# combined.net
KiCad netlist of a schematic drawn in EAGLE
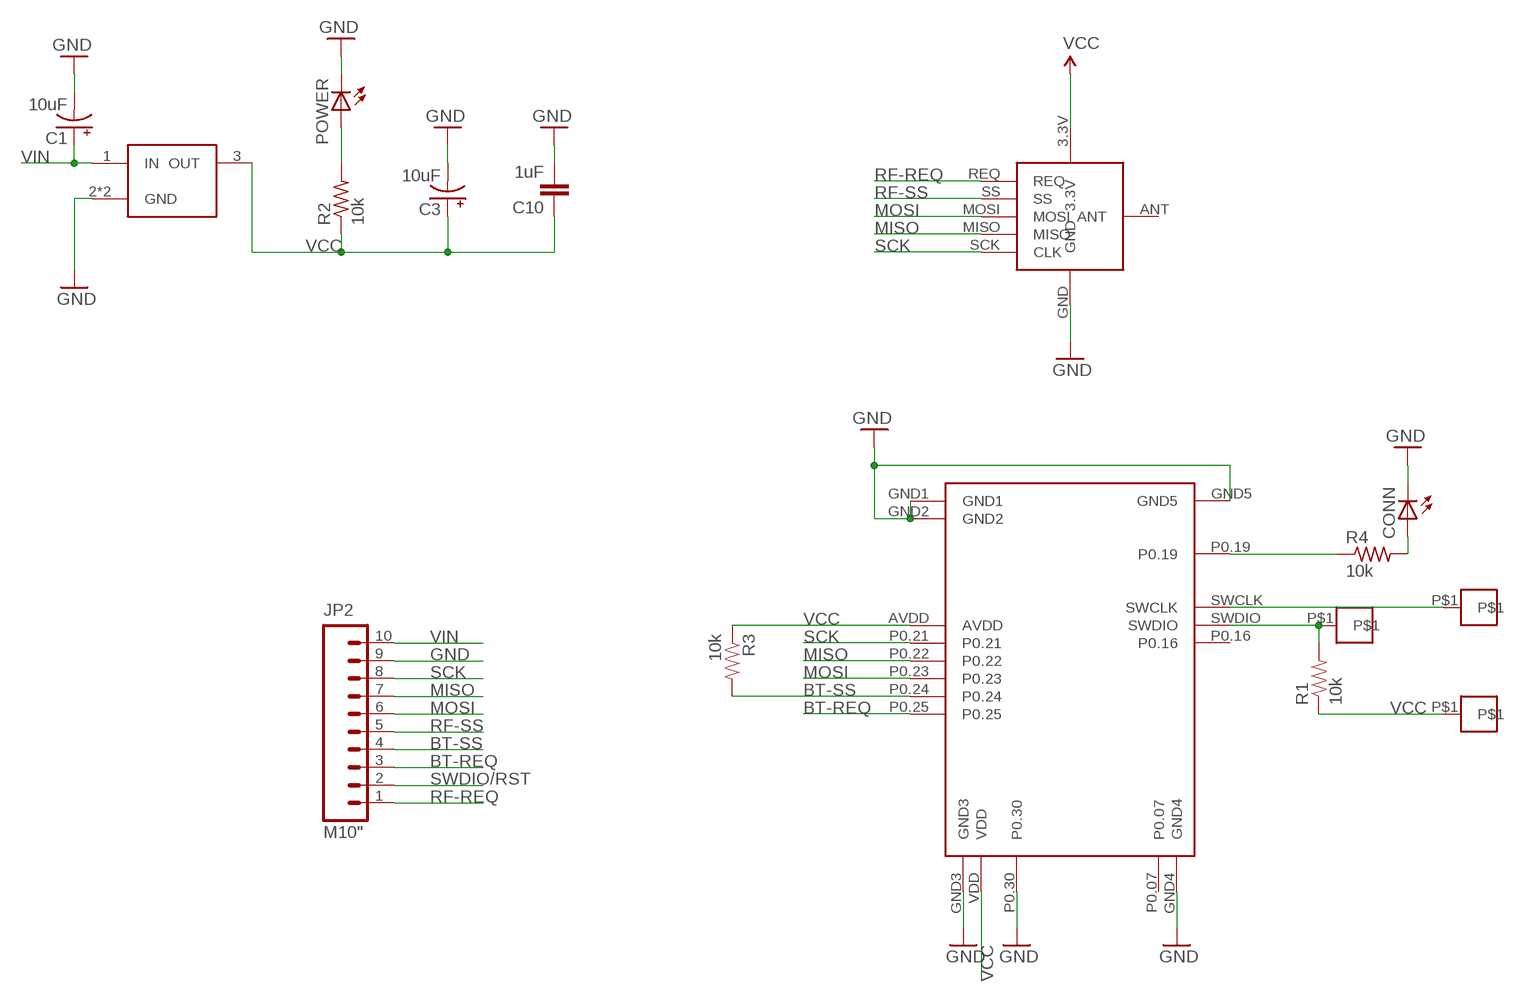
[diagram p0: schematic, sheet 1]

(export (version "E")
  (design (tool "Eeschema 10.0.6"))
  (components
    (comp (ref "C1")
      (value "10uF")
      (footprint "eagle-import:EIA3216")
      (libsource (lib "eagle-import") (part "CAP_POL1206"))
    )
    (comp (ref "C3")
      (value "10uF")
      (footprint "eagle-import:EIA3216")
      (libsource (lib "eagle-import") (part "CAP_POL1206"))
    )
    (comp (ref "C10")
      (value "1uF")
      (footprint "eagle-import:0603-CAP")
      (libsource (lib "eagle-import") (part "CAP0603-CAP"))
    )
    (comp (ref "CLOCK")
      (value "PAD")
      (footprint "eagle-import:SMD-ROUND")
      (libsource (lib "eagle-import") (part "PAD"))
    )
    (comp (ref "CLOCK1")
      (value "PAD")
      (footprint "eagle-import:SMD-ROUND")
      (libsource (lib "eagle-import") (part "PAD"))
    )
    (comp (ref "CONN")
      (value "LEDCHIP-LED0603")
      (footprint "eagle-import:CHIP-LED0603")
      (libsource (lib "eagle-import") (part "LEDCHIP-LED0603"))
    )
    (comp (ref "JP2")
      (value "M10\"")
      (footprint "eagle-import:1X10")
      (libsource (lib "eagle-import") (part "M10{dblquote}"))
    )
    (comp (ref "POWER")
      (value "LEDCHIP-LED0603")
      (footprint "eagle-import:CHIP-LED0603")
      (libsource (lib "eagle-import") (part "LEDCHIP-LED0603"))
    )
    (comp (ref "R1")
      (value "10k")
      (footprint "eagle-import:0603-RES")
      (libsource (lib "eagle-import") (part "RESISTOR0603"))
    )
    (comp (ref "R2")
      (value "10k")
      (footprint "eagle-import:R0603")
      (libsource (lib "eagle-import") (part "R-US_R0603"))
    )
    (comp (ref "R3")
      (value "10k")
      (footprint "eagle-import:0603-RES")
      (libsource (lib "eagle-import") (part "RESISTOR0603"))
    )
    (comp (ref "R4")
      (value "10k")
      (footprint "eagle-import:R0603")
      (libsource (lib "eagle-import") (part "R-US_R0603"))
    )
    (comp (ref "U$1")
      (value "RFM69")
      (footprint "eagle-import:S0C-RFM69")
      (libsource (lib "eagle-import") (part "RFM69"))
    )
    (comp (ref "U$3")
      (value "REGULATOR3.3V-UA78M33CDCYR")
      (footprint "eagle-import:SOT223")
      (libsource (lib "eagle-import") (part "REGULATOR3.3V-UA78M33CDCYR"))
    )
    (comp (ref "U$5")
      (value "NRF51-MDBT40-SPI")
      (footprint "eagle-import:SOC-NRF51-MDBT40-SPI")
      (libsource (lib "eagle-import") (part "NRF51-MDBT40-SPI"))
    )
    (comp (ref "VCC")
      (value "PAD")
      (footprint "eagle-import:SMD-ROUND")
      (libsource (lib "eagle-import") (part "PAD"))
    )
  )
  (nets
    (net (code "1") (name "/BT-REQ") (class "Default")
      (node (ref "JP2") (pin "3") (pinfunction "3_3") (pintype "passive"))
      (node (ref "U$5") (pin "P0.25") (pinfunction "P0.25_P0.25") (pintype "bidirectional"))
    )
    (net (code "2") (name "/BT-SS") (class "Default")
      (node (ref "JP2") (pin "4") (pinfunction "4_4") (pintype "passive"))
      (node (ref "R3") (pin "2") (pinfunction "2_2") (pintype "passive"))
      (node (ref "U$5") (pin "P0.24") (pinfunction "P0.24_P0.24") (pintype "bidirectional"))
    )
    (net (code "3") (name "/MISO") (class "Default")
      (node (ref "JP2") (pin "7") (pinfunction "7_7") (pintype "passive"))
      (node (ref "U$1") (pin "MISO") (pinfunction "MISO_MISO") (pintype "bidirectional"))
      (node (ref "U$5") (pin "P0.22") (pinfunction "P0.22_P0.22") (pintype "bidirectional"))
    )
    (net (code "4") (name "/MOSI") (class "Default")
      (node (ref "JP2") (pin "6") (pinfunction "6_6") (pintype "passive"))
      (node (ref "U$1") (pin "MOSI") (pinfunction "MOSI_MOSI") (pintype "bidirectional"))
      (node (ref "U$5") (pin "P0.23") (pinfunction "P0.23_P0.23") (pintype "bidirectional"))
    )
    (net (code "5") (name "/RF-REQ") (class "Default")
      (node (ref "JP2") (pin "1") (pinfunction "1_1") (pintype "passive"))
      (node (ref "U$1") (pin "REQ") (pinfunction "REQ_REQ") (pintype "bidirectional"))
    )
    (net (code "6") (name "/RF-SS") (class "Default")
      (node (ref "JP2") (pin "5") (pinfunction "5_5") (pintype "passive"))
      (node (ref "U$1") (pin "SS") (pinfunction "SS_SS") (pintype "bidirectional"))
    )
    (net (code "7") (name "/SCK") (class "Default")
      (node (ref "JP2") (pin "8") (pinfunction "8_8") (pintype "passive"))
      (node (ref "U$1") (pin "SCK") (pinfunction "CLK_SCK") (pintype "bidirectional"))
      (node (ref "U$5") (pin "P0.21") (pinfunction "P0.21_P0.21") (pintype "bidirectional"))
    )
    (net (code "8") (name "/SWDIO{slash}RST") (class "Default")
      (node (ref "CLOCK1") (pin "P$1") (pinfunction "P$1_P$1") (pintype "bidirectional"))
      (node (ref "JP2") (pin "2") (pinfunction "2_2") (pintype "passive"))
      (node (ref "R1") (pin "2") (pinfunction "2_2") (pintype "passive"))
      (node (ref "U$5") (pin "SWDIO") (pinfunction "SWDIO_SWDIO") (pintype "bidirectional"))
    )
    (net (code "9") (name "/VIN") (class "Default")
      (node (ref "C1") (pin "A") (pinfunction "+_A") (pintype "passive"))
      (node (ref "JP2") (pin "10") (pinfunction "10_10") (pintype "passive"))
      (node (ref "U$3") (pin "1") (pinfunction "IN_1") (pintype "bidirectional"))
    )
    (net (code "10") (name "GND") (class "Default")
      (node (ref "C1") (pin "C") (pinfunction "-_C") (pintype "passive"))
      (node (ref "C10") (pin "2") (pinfunction "2_2") (pintype "passive"))
      (node (ref "C3") (pin "C") (pinfunction "-_C") (pintype "passive"))
      (node (ref "CONN") (pin "C") (pinfunction "C_C") (pintype "passive"))
      (node (ref "JP2") (pin "9") (pinfunction "9_9") (pintype "passive"))
      (node (ref "POWER") (pin "C") (pinfunction "C_C") (pintype "passive"))
      (node (ref "U$1") (pin "GND") (pinfunction "GND_GND") (pintype "bidirectional"))
      (node (ref "U$3") (pin "2") (pinfunction "GND_2") (pintype "bidirectional"))
      (node (ref "U$3") (pin "4") (pinfunction "GND_4") (pintype "bidirectional"))
      (node (ref "U$5") (pin "GND1") (pinfunction "GND1_GND1") (pintype "bidirectional"))
      (node (ref "U$5") (pin "GND2") (pinfunction "GND2_GND2") (pintype "bidirectional"))
      (node (ref "U$5") (pin "GND3") (pinfunction "GND3_GND3") (pintype "bidirectional"))
      (node (ref "U$5") (pin "GND4") (pinfunction "GND4_GND4") (pintype "bidirectional"))
      (node (ref "U$5") (pin "GND5") (pinfunction "GND5_GND5") (pintype "bidirectional"))
      (node (ref "U$5") (pin "P0.30") (pinfunction "P0.30_P0.30") (pintype "bidirectional"))
    )
    (net (code "11") (name "Net-(CLOCK-PadP$1)") (class "Default")
      (node (ref "CLOCK") (pin "P$1") (pinfunction "P$1_P$1") (pintype "bidirectional"))
      (node (ref "U$5") (pin "SWCLK") (pinfunction "SWCLK_SWCLK") (pintype "bidirectional"))
    )
    (net (code "12") (name "Net-(CONN-PadA)") (class "Default")
      (node (ref "CONN") (pin "A") (pinfunction "A_A") (pintype "passive"))
      (node (ref "R4") (pin "2") (pinfunction "2_2") (pintype "passive"))
    )
    (net (code "13") (name "Net-(POWER-PadA)") (class "Default")
      (node (ref "POWER") (pin "A") (pinfunction "A_A") (pintype "passive"))
      (node (ref "R2") (pin "2") (pinfunction "2_2") (pintype "passive"))
    )
    (net (code "14") (name "Net-(R4-Pad1)") (class "Default")
      (node (ref "R4") (pin "1") (pinfunction "1_1") (pintype "passive"))
      (node (ref "U$5") (pin "P0.19") (pinfunction "P0.19_P0.19") (pintype "bidirectional"))
    )
    (net (code "15") (name "VCC") (class "Default")
      (node (ref "C10") (pin "1") (pinfunction "1_1") (pintype "passive"))
      (node (ref "C3") (pin "A") (pinfunction "+_A") (pintype "passive"))
      (node (ref "R1") (pin "1") (pinfunction "1_1") (pintype "passive"))
      (node (ref "R2") (pin "1") (pinfunction "1_1") (pintype "passive"))
      (node (ref "R3") (pin "1") (pinfunction "1_1") (pintype "passive"))
      (node (ref "U$1") (pin "3.3V") (pinfunction "3.3V_3.3V") (pintype "bidirectional"))
      (node (ref "U$3") (pin "3") (pinfunction "OUT_3") (pintype "bidirectional"))
      (node (ref "U$5") (pin "AVDD") (pinfunction "AVDD_AVDD") (pintype "bidirectional"))
      (node (ref "U$5") (pin "VDD") (pinfunction "VDD_VDD") (pintype "bidirectional"))
      (node (ref "VCC") (pin "P$1") (pinfunction "P$1_P$1") (pintype "bidirectional"))
    )
    (net (code "16") (name "unconnected-(U$1-PadANT)") (class "Default")
      (node (ref "U$1") (pin "ANT") (pinfunction "ANT_ANT") (pintype "bidirectional"))
    )
    (net (code "17") (name "unconnected-(U$5-PadP0.07)") (class "Default")
      (node (ref "U$5") (pin "P0.07") (pinfunction "P0.07_P0.07") (pintype "bidirectional"))
    )
    (net (code "18") (name "unconnected-(U$5-PadP0.16)") (class "Default")
      (node (ref "U$5") (pin "P0.16") (pinfunction "P0.16_P0.16") (pintype "bidirectional"))
    )
  )
)
